# FuenteCompleta.net
KiCad netlist of a schematic drawn in Altium Designer
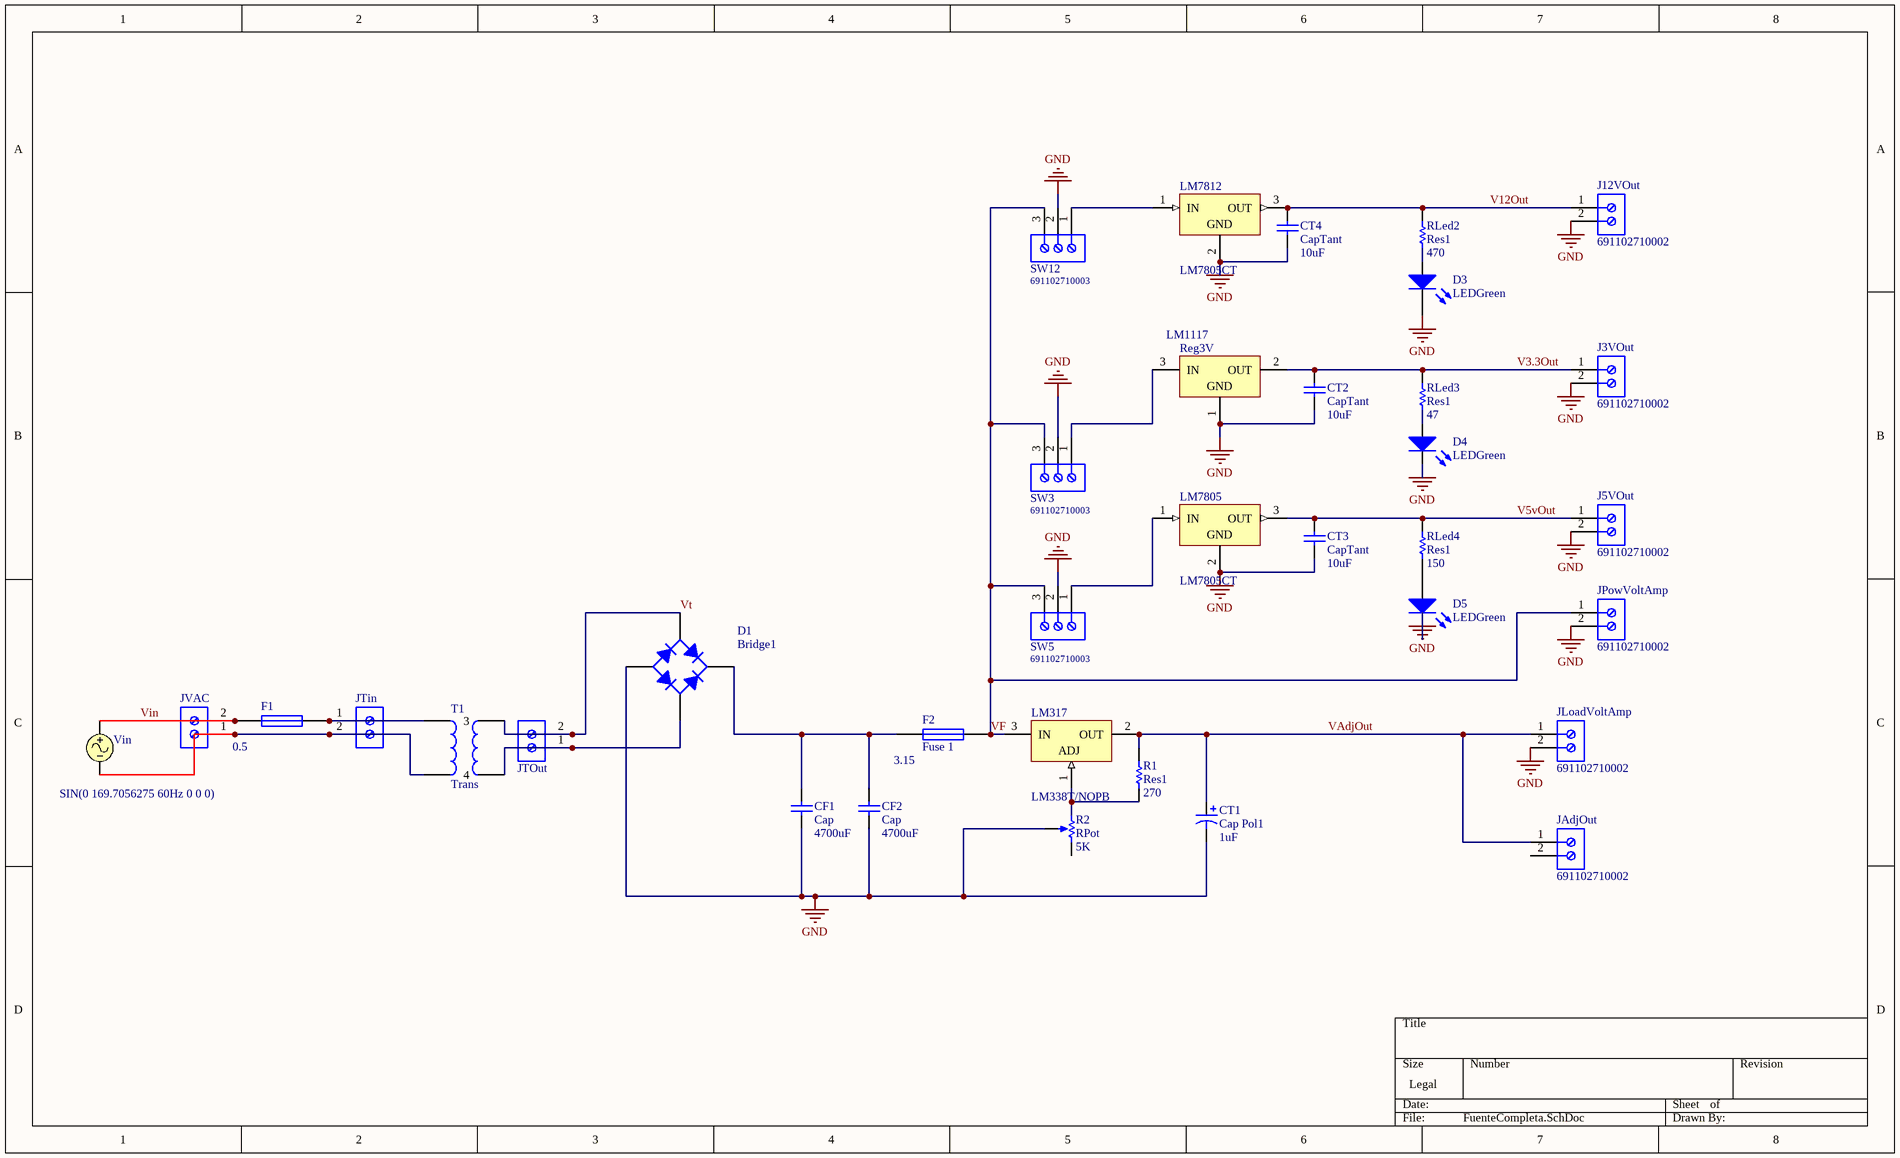
[diagram p0: FuenteCompleta.SchDoc]

(export (version "E")
  (design (tool "Eeschema 10.0.6"))
  (components
    (comp (ref "CF1")
      (value "Cap")
      (footprint "4700uF")
      (description "Capacitor")
      (fields (field (name "ALTIUM_VALUE") "4700uF") (field (name "PUBLISHER") "Altium Limited"))
      (libsource (lib "Miscellaneous Devices") (part "Cap"))
    )
    (comp (ref "CF2")
      (value "Cap")
      (footprint "4700uF")
      (description "Capacitor")
      (fields (field (name "ALTIUM_VALUE") "4700uF") (field (name "PUBLISHER") "Altium Limited"))
      (libsource (lib "Miscellaneous Devices") (part "Cap"))
    )
    (comp (ref "CT1")
      (value "Cap Pol1")
      (footprint "CAPPRD200W50D500H1250")
      (description "Polarized Capacitor (Radial)")
      (fields (field (name "ALTIUM_VALUE") "1uF") (field (name "PUBLISHER") "Altium Limited"))
      (libsource (lib "Miscellaneous Devices") (part "Cap Pol1"))
    )
    (comp (ref "CT2")
      (value "CapTant")
      (footprint "RAD-0.3")
      (description "Capacitor")
      (fields (field (name "ALTIUM_VALUE") "10uF") (field (name "PUBLISHER") "Altium Limited"))
      (libsource (lib "Miscellaneous Devices") (part "Cap"))
    )
    (comp (ref "CT3")
      (value "CapTant")
      (footprint "RAD-0.3")
      (description "Capacitor")
      (fields (field (name "ALTIUM_VALUE") "10uF") (field (name "PUBLISHER") "Altium Limited"))
      (libsource (lib "Miscellaneous Devices") (part "Cap"))
    )
    (comp (ref "CT4")
      (value "CapTant")
      (footprint "RAD-0.3")
      (description "Capacitor")
      (fields (field (name "ALTIUM_VALUE") "10uF") (field (name "PUBLISHER") "Altium Limited"))
      (libsource (lib "Miscellaneous Devices") (part "Cap"))
    )
    (comp (ref "D1")
      (value "Bridge1")
      (footprint "DIOB_GBJ2510")
      (description "Full Wave Diode Bridge")
      (fields (field (name "PUBLISHER") "Altium Limited"))
      (libsource (lib "Miscellaneous Devices") (part "Bridge1"))
    )
    (comp (ref "D3")
      (value "LEDGreen")
      (footprint "LEDRD254W57D500H1070")
      (description "Typical RED, GREEN, YELLOW, AMBER GaAs LED")
      (fields (field (name "PUBLISHER") "Altium Limited"))
      (libsource (lib "Miscellaneous Devices") (part "LED2"))
    )
    (comp (ref "D4")
      (value "LEDGreen")
      (footprint "LEDRD254W57D500H1070")
      (description "Typical RED, GREEN, YELLOW, AMBER GaAs LED")
      (fields (field (name "PUBLISHER") "Altium Limited"))
      (libsource (lib "Miscellaneous Devices") (part "LED2"))
    )
    (comp (ref "D5")
      (value "LEDGreen")
      (footprint "LEDRD254W57D500H1070")
      (description "Typical RED, GREEN, YELLOW, AMBER GaAs LED")
      (fields (field (name "PUBLISHER") "Altium Limited"))
      (libsource (lib "Miscellaneous Devices") (part "LED2"))
    )
    (comp (ref "F1")
      (value "Fuse 1")
      (footprint "PIN-W2/E2.8")
      (description "Fuse")
      (fields (field (name "CURRENT") "0.5") (field (name "PUBLISHER") "Altium Limited"))
      (libsource (lib "Miscellaneous Devices") (part "Fuse 1"))
    )
    (comp (ref "F2")
      (value "Fuse 1")
      (footprint "PIN-W2/E2.8")
      (description "Fuse")
      (fields (field (name "CURRENT") "3.15") (field (name "PUBLISHER") "Altium Limited"))
      (libsource (lib "Miscellaneous Devices") (part "Fuse 1"))
    )
    (comp (ref "J3VOut")
      (value "691102710002")
      (footprint "691102710002")
      (description "Series 102 - 5.00 mm Horizontal Entry Modular with Pressure Clamp WR-TBL, 2 pin")
      (fields (field (name "MANUFACTURER") "Wurth Elektronik") (field (name "PUBLISHER") "WurthElektronik"))
      (libsource (lib "Altium Content Vault") (part "WE-CN-1P-F-TB2"))
    )
    (comp (ref "J5VOut")
      (value "691102710002")
      (footprint "691102710002")
      (description "Series 102 - 5.00 mm Horizontal Entry Modular with Pressure Clamp WR-TBL, 2 pin")
      (fields (field (name "MANUFACTURER") "Wurth Elektronik") (field (name "PUBLISHER") "WurthElektronik"))
      (libsource (lib "Altium Content Vault") (part "WE-CN-1P-F-TB2"))
    )
    (comp (ref "J12VOut")
      (value "691102710002")
      (footprint "691102710002")
      (description "Series 102 - 5.00 mm Horizontal Entry Modular with Pressure Clamp WR-TBL, 2 pin")
      (fields (field (name "MANUFACTURER") "Wurth Elektronik") (field (name "PUBLISHER") "WurthElektronik"))
      (libsource (lib "Altium Content Vault") (part "WE-CN-1P-F-TB2"))
    )
    (comp (ref "JAdjOut")
      (value "691102710002")
      (footprint "691102710002")
      (description "Series 102 - 5.00 mm Horizontal Entry Modular with Pressure Clamp WR-TBL, 2 pin")
      (fields (field (name "MANUFACTURER") "Wurth Elektronik") (field (name "PUBLISHER") "WurthElektronik"))
      (libsource (lib "Altium Content Vault") (part "WE-CN-1P-F-TB2"))
    )
    (comp (ref "JLoadVoltAmp")
      (value "691102710002")
      (footprint "691102710002")
      (description "Series 102 - 5.00 mm Horizontal Entry Modular with Pressure Clamp WR-TBL, 2 pin")
      (fields (field (name "MANUFACTURER") "Wurth Elektronik") (field (name "PUBLISHER") "WurthElektronik"))
      (libsource (lib "Altium Content Vault") (part "WE-CN-1P-F-TB2"))
    )
    (comp (ref "JPowVoltAmp")
      (value "691102710002")
      (footprint "691102710002")
      (description "Series 102 - 5.00 mm Horizontal Entry Modular with Pressure Clamp WR-TBL, 2 pin")
      (fields (field (name "MANUFACTURER") "Wurth Elektronik") (field (name "PUBLISHER") "WurthElektronik"))
      (libsource (lib "Altium Content Vault") (part "WE-CN-1P-F-TB2"))
    )
    (comp (ref "JTin")
      (value "691102710002")
      (footprint "691102710002")
      (description "Series 102 - 5.00 mm Horizontal Entry Modular with Pressure Clamp WR-TBL, 2 pin")
      (fields (field (name "MANUFACTURER") "Wurth Elektronik") (field (name "PUBLISHER") "WurthElektronik"))
      (libsource (lib "Altium Content Vault") (part "WE-CN-1P-F-TB2"))
    )
    (comp (ref "JTOut")
      (value "691102710002")
      (footprint "691102710002")
      (description "Series 102 - 5.00 mm Horizontal Entry Modular with Pressure Clamp WR-TBL, 2 pin")
      (fields (field (name "MANUFACTURER") "Wurth Elektronik") (field (name "PUBLISHER") "WurthElektronik"))
      (libsource (lib "Altium Content Vault") (part "WE-CN-1P-F-TB2"))
    )
    (comp (ref "JVAC")
      (value "691102710002")
      (footprint "691102710002")
      (description "Series 102 - 5.00 mm Horizontal Entry Modular with Pressure Clamp WR-TBL, 2 pin")
      (fields (field (name "MANUFACTURER") "Wurth Elektronik") (field (name "PUBLISHER") "WurthElektronik"))
      (libsource (lib "Altium Content Vault") (part "WE-CN-1P-F-TB2"))
    )
    (comp (ref "LM317")
      (value "LM338T/NOPB")
      (footprint "NDE0003A")
      (description "5 Amp Adjustable Regulator, 3-pin TO-220, Pb-Free")
      (fields (field (name "MANUFACTURER") "Texas Instruments"))
      (libsource (lib "Altium Content Vault") (part "PM-REG-LM1086ADJ-SIL3"))
    )
    (comp (ref "LM7805")
      (value "LM7805CT")
      (footprint "FAIR-TO-220-3")
      (description "Positive Voltage Regulator, 5 V, 1 A, -40 to 125 degC, 3-Pin TO-220, RoHS, Tube")
      (fields (field (name "MANUFACTURER") "FairchildSemiconductor"))
      (libsource (lib "Altium Content Vault") (part "FAIR-LM7805CT-TO220-3"))
    )
    (comp (ref "LM7812")
      (value "LM7805CT")
      (footprint "FAIR-TO-220-3")
      (description "Positive Voltage Regulator, 5 V, 1 A, -40 to 125 degC, 3-Pin TO-220, RoHS, Tube")
      (fields (field (name "MANUFACTURER") "FairchildSemiconductor"))
      (libsource (lib "Altium Content Vault") (part "FAIR-LM7805CT-TO220-3"))
    )
    (comp (ref "R1")
      (value "Res1")
      (footprint "AXIAL-0.3")
      (description "Resistor")
      (fields (field (name "ALTIUM_VALUE") "270") (field (name "PUBLISHER") "Altium Limited"))
      (libsource (lib "Miscellaneous Devices") (part "Res1"))
    )
    (comp (ref "R2")
      (value "RPot")
      (footprint "VR5")
      (description "Potentiometer")
      (fields (field (name "ALTIUM_VALUE") "5K") (field (name "PUBLISHER") "Altium Limited"))
      (libsource (lib "Miscellaneous Devices") (part "RPot"))
    )
    (comp (ref "Reg3V")
      (value "LM1117")
      (footprint "NDE0003A")
      (description "5A Low Dropout Positive Regulators, 3-pin TO-220, Pb-Free")
      (fields (field (name "MANUFACTURER") "Texas Instruments"))
      (libsource (lib "Altium Content Vault") (part "PM-REG-LM1086-SIL3"))
    )
    (comp (ref "RLed2")
      (value "Res1")
      (footprint "AXIAL-0.3")
      (description "Resistor")
      (fields (field (name "ALTIUM_VALUE") "470") (field (name "PUBLISHER") "Altium Limited"))
      (libsource (lib "Miscellaneous Devices") (part "Res1"))
    )
    (comp (ref "RLed3")
      (value "Res1")
      (footprint "AXIAL-0.3")
      (description "Resistor")
      (fields (field (name "ALTIUM_VALUE") "47") (field (name "PUBLISHER") "Altium Limited"))
      (libsource (lib "Miscellaneous Devices") (part "Res1"))
    )
    (comp (ref "RLed4")
      (value "Res1")
      (footprint "AXIAL-0.3")
      (description "Resistor")
      (fields (field (name "ALTIUM_VALUE") "150") (field (name "PUBLISHER") "Altium Limited"))
      (libsource (lib "Miscellaneous Devices") (part "Res1"))
    )
    (comp (ref "SW3")
      (value "691102710003")
      (footprint "691102710003")
      (description "Series 102 - 5.00 mm Horizontal Entry Modular with Pressure Clamp WR-TBL, 3 pin")
      (fields (field (name "MANUFACTURER") "Wurth Elektronik") (field (name "PUBLISHER") "WurthElektronik"))
      (libsource (lib "Altium Content Vault") (part "WE-CN-1P-F-TB3"))
    )
    (comp (ref "SW5")
      (value "691102710003")
      (footprint "691102710003")
      (description "Series 102 - 5.00 mm Horizontal Entry Modular with Pressure Clamp WR-TBL, 3 pin")
      (fields (field (name "MANUFACTURER") "Wurth Elektronik") (field (name "PUBLISHER") "WurthElektronik"))
      (libsource (lib "Altium Content Vault") (part "WE-CN-1P-F-TB3"))
    )
    (comp (ref "SW12")
      (value "691102710003")
      (footprint "691102710003")
      (description "Series 102 - 5.00 mm Horizontal Entry Modular with Pressure Clamp WR-TBL, 3 pin")
      (fields (field (name "MANUFACTURER") "Wurth Elektronik") (field (name "PUBLISHER") "WurthElektronik"))
      (libsource (lib "Altium Content Vault") (part "WE-CN-1P-F-TB3"))
    )
    (comp (ref "T1")
      (value "Trans")
      (description "Transformer")
      (fields (field (name "PUBLISHER") "Altium Limited"))
      (libsource (lib "Miscellaneous Devices") (part "Trans"))
    )
    (comp (ref "Vin")
      (value "SIN(0 169.7056275 60Hz 0 0 0)")
      (description "Sinusoidal Voltage Source")
      (fields (field (name "PUBLISHER") "Altium Limited"))
      (libsource (lib "Simulation Sources") (part "VSIN"))
    )
  )
  (nets
    (net (code "1") (name "/V3.3Out") (class "Default")
      (node (ref "CT2") (pin "2") (pinfunction "2_2") (pintype "passive"))
      (node (ref "J3VOut") (pin "1") (pinfunction "1_1") (pintype "passive"))
      (node (ref "RLed3") (pin "2") (pinfunction "2_2") (pintype "passive"))
      (node (ref "Reg3V") (pin "2") (pinfunction "OUT_2") (pintype "power_in"))
    )
    (net (code "2") (name "/V5vOut") (class "Default")
      (node (ref "CT3") (pin "2") (pinfunction "2_2") (pintype "passive"))
      (node (ref "J5VOut") (pin "1") (pinfunction "1_1") (pintype "passive"))
      (node (ref "LM7805") (pin "3") (pinfunction "OUT_3") (pintype "output"))
      (node (ref "RLed4") (pin "2") (pinfunction "2_2") (pintype "passive"))
    )
    (net (code "3") (name "/V12Out") (class "Default")
      (node (ref "CT4") (pin "2") (pinfunction "2_2") (pintype "passive"))
      (node (ref "J12VOut") (pin "1") (pinfunction "1_1") (pintype "passive"))
      (node (ref "LM7812") (pin "3") (pinfunction "OUT_3") (pintype "output"))
      (node (ref "RLed2") (pin "2") (pinfunction "2_2") (pintype "passive"))
    )
    (net (code "4") (name "/VAdjOut") (class "Default")
      (node (ref "CT1") (pin "1") (pinfunction "1_1") (pintype "passive"))
      (node (ref "JAdjOut") (pin "1") (pinfunction "1_1") (pintype "passive"))
      (node (ref "JLoadVoltAmp") (pin "1") (pinfunction "1_1") (pintype "passive"))
      (node (ref "LM317") (pin "2") (pinfunction "OUT_2") (pintype "power_in"))
      (node (ref "R1") (pin "2") (pinfunction "2_2") (pintype "passive"))
    )
    (net (code "5") (name "/VF") (class "Default")
      (node (ref "F2") (pin "2") (pinfunction "2_2") (pintype "passive"))
      (node (ref "JPowVoltAmp") (pin "1") (pinfunction "1_1") (pintype "passive"))
      (node (ref "LM317") (pin "3") (pinfunction "IN_3") (pintype "power_in"))
      (node (ref "SW12") (pin "3") (pinfunction "3_3") (pintype "passive"))
      (node (ref "SW3") (pin "3") (pinfunction "3_3") (pintype "passive"))
      (node (ref "SW5") (pin "3") (pinfunction "3_3") (pintype "passive"))
    )
    (net (code "6") (name "/Vin") (class "Default")
      (node (ref "F1") (pin "1") (pinfunction "1_1") (pintype "passive"))
      (node (ref "JVAC") (pin "2") (pinfunction "2_2") (pintype "passive"))
      (node (ref "Vin") (pin "1") (pinfunction "1_1") (pintype "passive"))
    )
    (net (code "7") (name "/Vt") (class "Default")
      (node (ref "D1") (pin "4") (pinfunction "C_4") (pintype "passive"))
      (node (ref "JTOut") (pin "2") (pinfunction "2_2") (pintype "passive"))
      (node (ref "T1") (pin "3") (pinfunction "3_3") (pintype "passive"))
    )
    (net (code "8") (name "GND") (class "Default")
      (node (ref "CF1") (pin "1") (pinfunction "1_1") (pintype "passive"))
      (node (ref "CF2") (pin "1") (pinfunction "1_1") (pintype "passive"))
      (node (ref "CT1") (pin "2") (pinfunction "2_2") (pintype "passive"))
      (node (ref "CT2") (pin "1") (pinfunction "1_1") (pintype "passive"))
      (node (ref "CT3") (pin "1") (pinfunction "1_1") (pintype "passive"))
      (node (ref "CT4") (pin "1") (pinfunction "1_1") (pintype "passive"))
      (node (ref "D1") (pin "3") (pinfunction "A_3") (pintype "passive"))
      (node (ref "D3") (pin "2") (pinfunction "K_2") (pintype "passive"))
      (node (ref "D4") (pin "2") (pinfunction "K_2") (pintype "passive"))
      (node (ref "D5") (pin "2") (pinfunction "K_2") (pintype "passive"))
      (node (ref "J12VOut") (pin "2") (pinfunction "2_2") (pintype "passive"))
      (node (ref "J3VOut") (pin "2") (pinfunction "2_2") (pintype "passive"))
      (node (ref "J5VOut") (pin "2") (pinfunction "2_2") (pintype "passive"))
      (node (ref "JLoadVoltAmp") (pin "2") (pinfunction "2_2") (pintype "passive"))
      (node (ref "JPowVoltAmp") (pin "2") (pinfunction "2_2") (pintype "passive"))
      (node (ref "LM7805") (pin "2") (pinfunction "GND_2") (pintype "power_in"))
      (node (ref "LM7812") (pin "2") (pinfunction "GND_2") (pintype "power_in"))
      (node (ref "R2") (pin "3") (pinfunction "TAP_3") (pintype "passive"))
      (node (ref "Reg3V") (pin "1") (pinfunction "GND_1") (pintype "power_in"))
      (node (ref "SW12") (pin "2") (pinfunction "2_2") (pintype "passive"))
      (node (ref "SW3") (pin "2") (pinfunction "2_2") (pintype "passive"))
      (node (ref "SW5") (pin "2") (pinfunction "2_2") (pintype "passive"))
    )
    (net (code "9") (name "Net-(D1-C-Pad2)") (class "Default")
      (node (ref "D1") (pin "2") (pinfunction "C_2") (pintype "passive"))
      (node (ref "JTOut") (pin "1") (pinfunction "1_1") (pintype "passive"))
      (node (ref "T1") (pin "4") (pinfunction "4_4") (pintype "passive"))
    )
    (net (code "10") (name "Net-(D1-K)") (class "Default")
      (node (ref "CF1") (pin "2") (pinfunction "2_2") (pintype "passive"))
      (node (ref "CF2") (pin "2") (pinfunction "2_2") (pintype "passive"))
      (node (ref "D1") (pin "1") (pinfunction "K_1") (pintype "passive"))
      (node (ref "F2") (pin "1") (pinfunction "1_1") (pintype "passive"))
    )
    (net (code "11") (name "Net-(D3-A)") (class "Default")
      (node (ref "D3") (pin "1") (pinfunction "A_1") (pintype "passive"))
      (node (ref "RLed2") (pin "1") (pinfunction "1_1") (pintype "passive"))
    )
    (net (code "12") (name "Net-(D4-A)") (class "Default")
      (node (ref "D4") (pin "1") (pinfunction "A_1") (pintype "passive"))
      (node (ref "RLed3") (pin "1") (pinfunction "1_1") (pintype "passive"))
    )
    (net (code "13") (name "Net-(D5-A)") (class "Default")
      (node (ref "D5") (pin "1") (pinfunction "A_1") (pintype "passive"))
      (node (ref "RLed4") (pin "1") (pinfunction "1_1") (pintype "passive"))
    )
    (net (code "14") (name "Net-(F1-Pad2)") (class "Default")
      (node (ref "F1") (pin "2") (pinfunction "2_2") (pintype "passive"))
      (node (ref "JTin") (pin "1") (pinfunction "1_1") (pintype "passive"))
      (node (ref "T1") (pin "1") (pinfunction "1_1") (pintype "passive"))
    )
    (net (code "15") (name "Net-(JTin-Pad2)") (class "Default")
      (node (ref "JTin") (pin "2") (pinfunction "2_2") (pintype "passive"))
      (node (ref "JVAC") (pin "1") (pinfunction "1_1") (pintype "passive"))
      (node (ref "T1") (pin "2") (pinfunction "2_2") (pintype "passive"))
      (node (ref "Vin") (pin "2") (pinfunction "2_2") (pintype "passive"))
    )
    (net (code "16") (name "Net-(LM317-ADJ)") (class "Default")
      (node (ref "LM317") (pin "1") (pinfunction "ADJ_1") (pintype "input"))
      (node (ref "R1") (pin "1") (pinfunction "1_1") (pintype "passive"))
      (node (ref "R2") (pin "1") (pinfunction "TOP_1") (pintype "passive"))
    )
    (net (code "17") (name "Net-(LM7805-IN)") (class "Default")
      (node (ref "LM7805") (pin "1") (pinfunction "IN_1") (pintype "input"))
      (node (ref "SW5") (pin "1") (pinfunction "1_1") (pintype "passive"))
    )
    (net (code "18") (name "Net-(LM7812-IN)") (class "Default")
      (node (ref "LM7812") (pin "1") (pinfunction "IN_1") (pintype "input"))
      (node (ref "SW12") (pin "1") (pinfunction "1_1") (pintype "passive"))
    )
    (net (code "19") (name "Net-(Reg3V-IN)") (class "Default")
      (node (ref "Reg3V") (pin "3") (pinfunction "IN_3") (pintype "power_in"))
      (node (ref "SW3") (pin "1") (pinfunction "1_1") (pintype "passive"))
    )
    (net (code "20") (name "unconnected-(JAdjOut-Pad2)") (class "Default")
      (node (ref "JAdjOut") (pin "2") (pinfunction "2_2") (pintype "passive"))
    )
    (net (code "21") (name "unconnected-(R2-BOT-Pad2)") (class "Default")
      (node (ref "R2") (pin "2") (pinfunction "BOT_2") (pintype "passive"))
    )
  )
)
